# Current_Sensor.net
KiCad netlist of a schematic drawn in Altium Designer
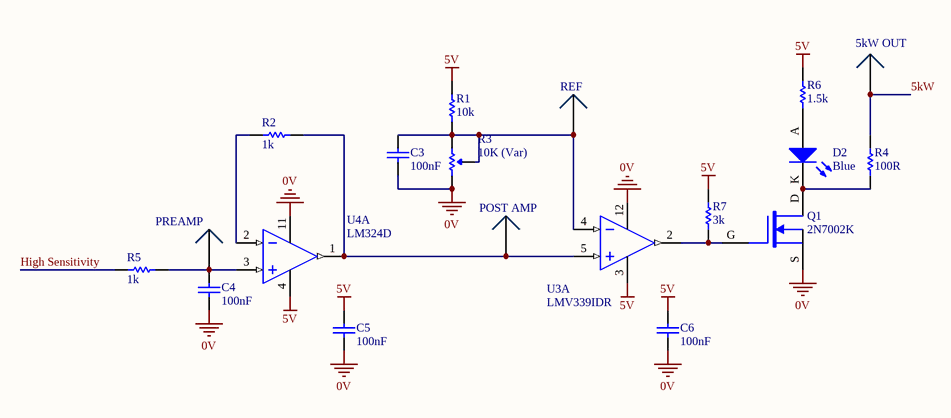
[diagram p0: Current Sensor.SchDoc]

(export (version "E")
  (design (tool "Eeschema 10.0.6"))
  (components
    (comp (ref "5kW OUT")
      (value "0mm")
      (footprint "TH Test Point")
      (fields (field (name "PART NUMBER") "TH Test Point") (field (name "CONTACT") "NA"))
      (libsource (lib "ts_20-standard-connectors") (part "Test Point"))
    )
    (comp (ref "C3")
      (value "100nF")
      (footprint "0805")
      (fields
        (field (name "PART NUMBER") "GCM21BR71E104KA37L")
        (field (name "TOLERANCE") "10%")
        (field (name "MANUFACTURER") "muRata")
      )
      (libsource (lib "ts_20-standard-library") (part "Capacitor"))
    )
    (comp (ref "C4")
      (value "100nF")
      (footprint "0805")
      (fields
        (field (name "PART NUMBER") "GCM21BR71E104KA37L")
        (field (name "TOLERANCE") "10%")
        (field (name "MANUFACTURER") "muRata")
      )
      (libsource (lib "ts_20-standard-library") (part "Capacitor"))
    )
    (comp (ref "C5")
      (value "100nF")
      (footprint "0805")
      (fields
        (field (name "PART NUMBER") "GCM21BR71E104KA37L")
        (field (name "TOLERANCE") "10%")
        (field (name "MANUFACTURER") "muRata")
      )
      (libsource (lib "ts_20-standard-library") (part "Capacitor"))
    )
    (comp (ref "C6")
      (value "100nF")
      (footprint "0805")
      (fields
        (field (name "PART NUMBER") "GCM21BR71E104KA37L")
        (field (name "TOLERANCE") "10%")
        (field (name "MANUFACTURER") "muRata")
      )
      (libsource (lib "ts_20-standard-library") (part "Capacitor"))
    )
    (comp (ref "D2")
      (value "Blue")
      (footprint "0805 LED")
      (description "LED BLUE CLEAR 2012 SMD")
      (fields
        (field (name "PART NUMBER") "SML-MN2BCTT86C")
        (field (name "MANUFACTURER") "ROHM Semiconductor")
      )
      (libsource (lib "ts_20-standard-library") (part "LED"))
    )
    (comp (ref "POST AMP")
      (value "0mm")
      (footprint "TH Test Point")
      (fields (field (name "PART NUMBER") "TH Test Point") (field (name "CONTACT") "NA"))
      (libsource (lib "ts_20-standard-connectors") (part "Test Point"))
    )
    (comp (ref "PREAMP")
      (value "0mm")
      (footprint "TH Test Point")
      (fields (field (name "PART NUMBER") "TH Test Point") (field (name "CONTACT") "NA"))
      (libsource (lib "ts_20-standard-connectors") (part "Test Point"))
    )
    (comp (ref "Q1")
      (value "2N7002K")
      (footprint "ON SOT-23 MOSFET")
      (description "60V 380mA, NFET MOSTFET (Small Signal)")
      (fields
        (field (name "MANUFACTURER") "ON Semiconductor")
        (field (name "DIGIKEY PART NUMBER") "2N7002KCT-ND")
        (field (name "PUBLISHER") "Altium Limited")
      )
      (libsource (lib "ts_20-standard-library") (part "MOSFET-N"))
    )
    (comp (ref "R1")
      (value "10k")
      (footprint "0805")
      (fields
        (field (name "PART NUMBER") "RC0805FR0710KL")
        (field (name "MANUFACTURER") "YAGEO")
        (field (name "TOLERANCE") "0.01")
      )
      (libsource (lib "ts_20-standard-library") (part "Resistor"))
    )
    (comp (ref "R2")
      (value "1k")
      (footprint "0805")
      (fields
        (field (name "PART NUMBER") "RC0805FR071KL")
        (field (name "MANUFACTURER") "YAGEO")
        (field (name "TOLERANCE") "0.01")
      )
      (libsource (lib "ts_20-standard-library") (part "Resistor"))
    )
    (comp (ref "R3")
      (value "10K (Var)")
      (footprint "B 3296")
      (fields
        (field (name "PART NUMBER") "3296W-1-103LF")
        (field (name "MANUFACTURER") "Bournes Inc")
        (field (name "TOLERANCE") "0.1")
      )
      (libsource (lib "ts_20-standard-library") (part "Resistor (Potentiometer)"))
    )
    (comp (ref "R4")
      (value "100R")
      (footprint "0805")
      (fields
        (field (name "PART NUMBER") "RC0805FR07100RL")
        (field (name "MANUFACTURER") "YAGEO")
        (field (name "TOLERANCE") "0.01")
      )
      (libsource (lib "ts_20-standard-library") (part "Resistor"))
    )
    (comp (ref "R5")
      (value "1k")
      (footprint "0805")
      (fields
        (field (name "PART NUMBER") "RC0805FR071KL")
        (field (name "MANUFACTURER") "YAGEO")
        (field (name "TOLERANCE") "0.01")
      )
      (libsource (lib "ts_20-standard-library") (part "Resistor"))
    )
    (comp (ref "R6")
      (value "1.5k")
      (footprint "0805")
      (fields
        (field (name "PART NUMBER") "RC0805FR071K5L")
        (field (name "MANUFACTURER") "YAGEO")
        (field (name "TOLERANCE") "0.01")
      )
      (libsource (lib "ts_20-standard-library") (part "Resistor"))
    )
    (comp (ref "R7")
      (value "3k")
      (footprint "0805")
      (fields
        (field (name "PART NUMBER") "RC0805FR073KL")
        (field (name "MANUFACTURER") "YAGEO")
        (field (name "TOLERANCE") "0.01")
      )
      (libsource (lib "ts_20-standard-library") (part "Resistor"))
    )
    (comp (ref "REF")
      (value "0mm")
      (footprint "TH Test Point")
      (fields (field (name "PART NUMBER") "TH Test Point") (field (name "CONTACT") "NA"))
      (libsource (lib "ts_20-standard-connectors") (part "Test Point"))
    )
    (comp (ref "U3")
      (value "LMV339IDR")
      (footprint "TI 14-SOIC")
      (description "Comparator General Purpose Open Collector 14-SOIC")
      (fields
        (field (name "MANUFACTURER") "Texas Instruments")
        (field (name "DIGIKEY PART NUMBER") "296-6611-2-ND")
      )
      (libsource (lib "ts_20-standard-library") (part "LMV339IDR"))
    )
    (comp (ref "U4")
      (value "LM324D")
      (footprint "TI 14-SOIC")
      (description "IC OPAMP GP 4 CIRCUIT 14SOIC")
      (fields
        (field (name "MANUFACTURER") "Texas Instruments")
        (field (name "DIGIKEY PART NUMBER") "296-1390-5-ND")
      )
      (libsource (lib "ts_20-standard-library") (part "LM324D"))
    )
  )
  (nets
    (net (code "1") (name "/5kW") (class "Default")
      (node (ref "5kW OUT") (pin "1") (pinfunction "1_1") (pintype "passive"))
      (node (ref "R4") (pin "2") (pinfunction "2_2") (pintype "passive"))
    )
    (net (code "2") (name "/High Sensitivity") (class "Default")
      (node (ref "R5") (pin "1") (pinfunction "1_1") (pintype "passive"))
    )
    (net (code "3") (name "0V") (class "Default")
      (node (ref "C3") (pin "1") (pinfunction "1_1") (pintype "passive"))
      (node (ref "C4") (pin "1") (pinfunction "1_1") (pintype "passive"))
      (node (ref "C5") (pin "1") (pinfunction "1_1") (pintype "passive"))
      (node (ref "C6") (pin "1") (pinfunction "1_1") (pintype "passive"))
      (node (ref "Q1") (pin "S") (pinfunction "S_S") (pintype "passive"))
      (node (ref "R3") (pin "3") (pinfunction "CW_3") (pintype "passive"))
      (node (ref "U3") (pin "12") (pinfunction "V-_12") (pintype "power_in"))
      (node (ref "U4") (pin "11") (pinfunction "GND_11") (pintype "power_in"))
    )
    (net (code "4") (name "5V") (class "Default")
      (node (ref "C5") (pin "2") (pinfunction "2_2") (pintype "passive"))
      (node (ref "C6") (pin "2") (pinfunction "2_2") (pintype "passive"))
      (node (ref "R1") (pin "2") (pinfunction "2_2") (pintype "passive"))
      (node (ref "R6") (pin "2") (pinfunction "2_2") (pintype "passive"))
      (node (ref "R7") (pin "2") (pinfunction "2_2") (pintype "passive"))
      (node (ref "U3") (pin "3") (pinfunction "V+_3") (pintype "power_in"))
      (node (ref "U4") (pin "4") (pinfunction "VCC_4") (pintype "power_in"))
    )
    (net (code "5") (name "Net-(C4-Pad2)") (class "Default")
      (node (ref "C4") (pin "2") (pinfunction "2_2") (pintype "passive"))
      (node (ref "PREAMP") (pin "1") (pinfunction "1_1") (pintype "passive"))
      (node (ref "R5") (pin "2") (pinfunction "2_2") (pintype "passive"))
      (node (ref "U4") (pin "3") (pinfunction "1IN+_3") (pintype "input"))
    )
    (net (code "6") (name "Net-(D2-PadA)") (class "Default")
      (node (ref "D2") (pin "A") (pinfunction "A_A") (pintype "passive"))
      (node (ref "R6") (pin "1") (pinfunction "1_1") (pintype "passive"))
    )
    (net (code "7") (name "Net-(D2-PadK)") (class "Default")
      (node (ref "D2") (pin "K") (pinfunction "K_K") (pintype "passive"))
      (node (ref "Q1") (pin "D") (pinfunction "D_D") (pintype "passive"))
      (node (ref "R4") (pin "1") (pinfunction "1_1") (pintype "passive"))
    )
    (net (code "8") (name "Net-(R2-Pad1)") (class "Default")
      (node (ref "R2") (pin "1") (pinfunction "1_1") (pintype "passive"))
      (node (ref "U4") (pin "2") (pinfunction "1IN+_2") (pintype "input"))
    )
    (net (code "9") (name "Net-(R3-CCW)") (class "Default")
      (node (ref "C3") (pin "2") (pinfunction "2_2") (pintype "passive"))
      (node (ref "R1") (pin "1") (pinfunction "1_1") (pintype "passive"))
      (node (ref "R3") (pin "1") (pinfunction "CCW_1") (pintype "passive"))
      (node (ref "R3") (pin "2") (pinfunction "Wiper_2") (pintype "passive"))
      (node (ref "REF") (pin "1") (pinfunction "1_1") (pintype "passive"))
      (node (ref "U3") (pin "4") (pinfunction "IN_A-_4") (pintype "input"))
    )
    (net (code "10") (name "Net-(U3A-IN_A+)") (class "Default")
      (node (ref "POST AMP") (pin "1") (pinfunction "1_1") (pintype "passive"))
      (node (ref "R2") (pin "2") (pinfunction "2_2") (pintype "passive"))
      (node (ref "U3") (pin "5") (pinfunction "IN_A+_5") (pintype "input"))
      (node (ref "U4") (pin "1") (pinfunction "1OUT_1") (pintype "output"))
    )
    (net (code "11") (name "Net-(U3A-OUT_A)") (class "Default")
      (node (ref "Q1") (pin "G") (pinfunction "G_G") (pintype "passive"))
      (node (ref "R7") (pin "1") (pinfunction "1_1") (pintype "passive"))
      (node (ref "U3") (pin "2") (pinfunction "OUT_A_2") (pintype "output"))
    )
  )
)
